# G1000_Base.net
KiCad netlist of a schematic drawn in EasyEDA
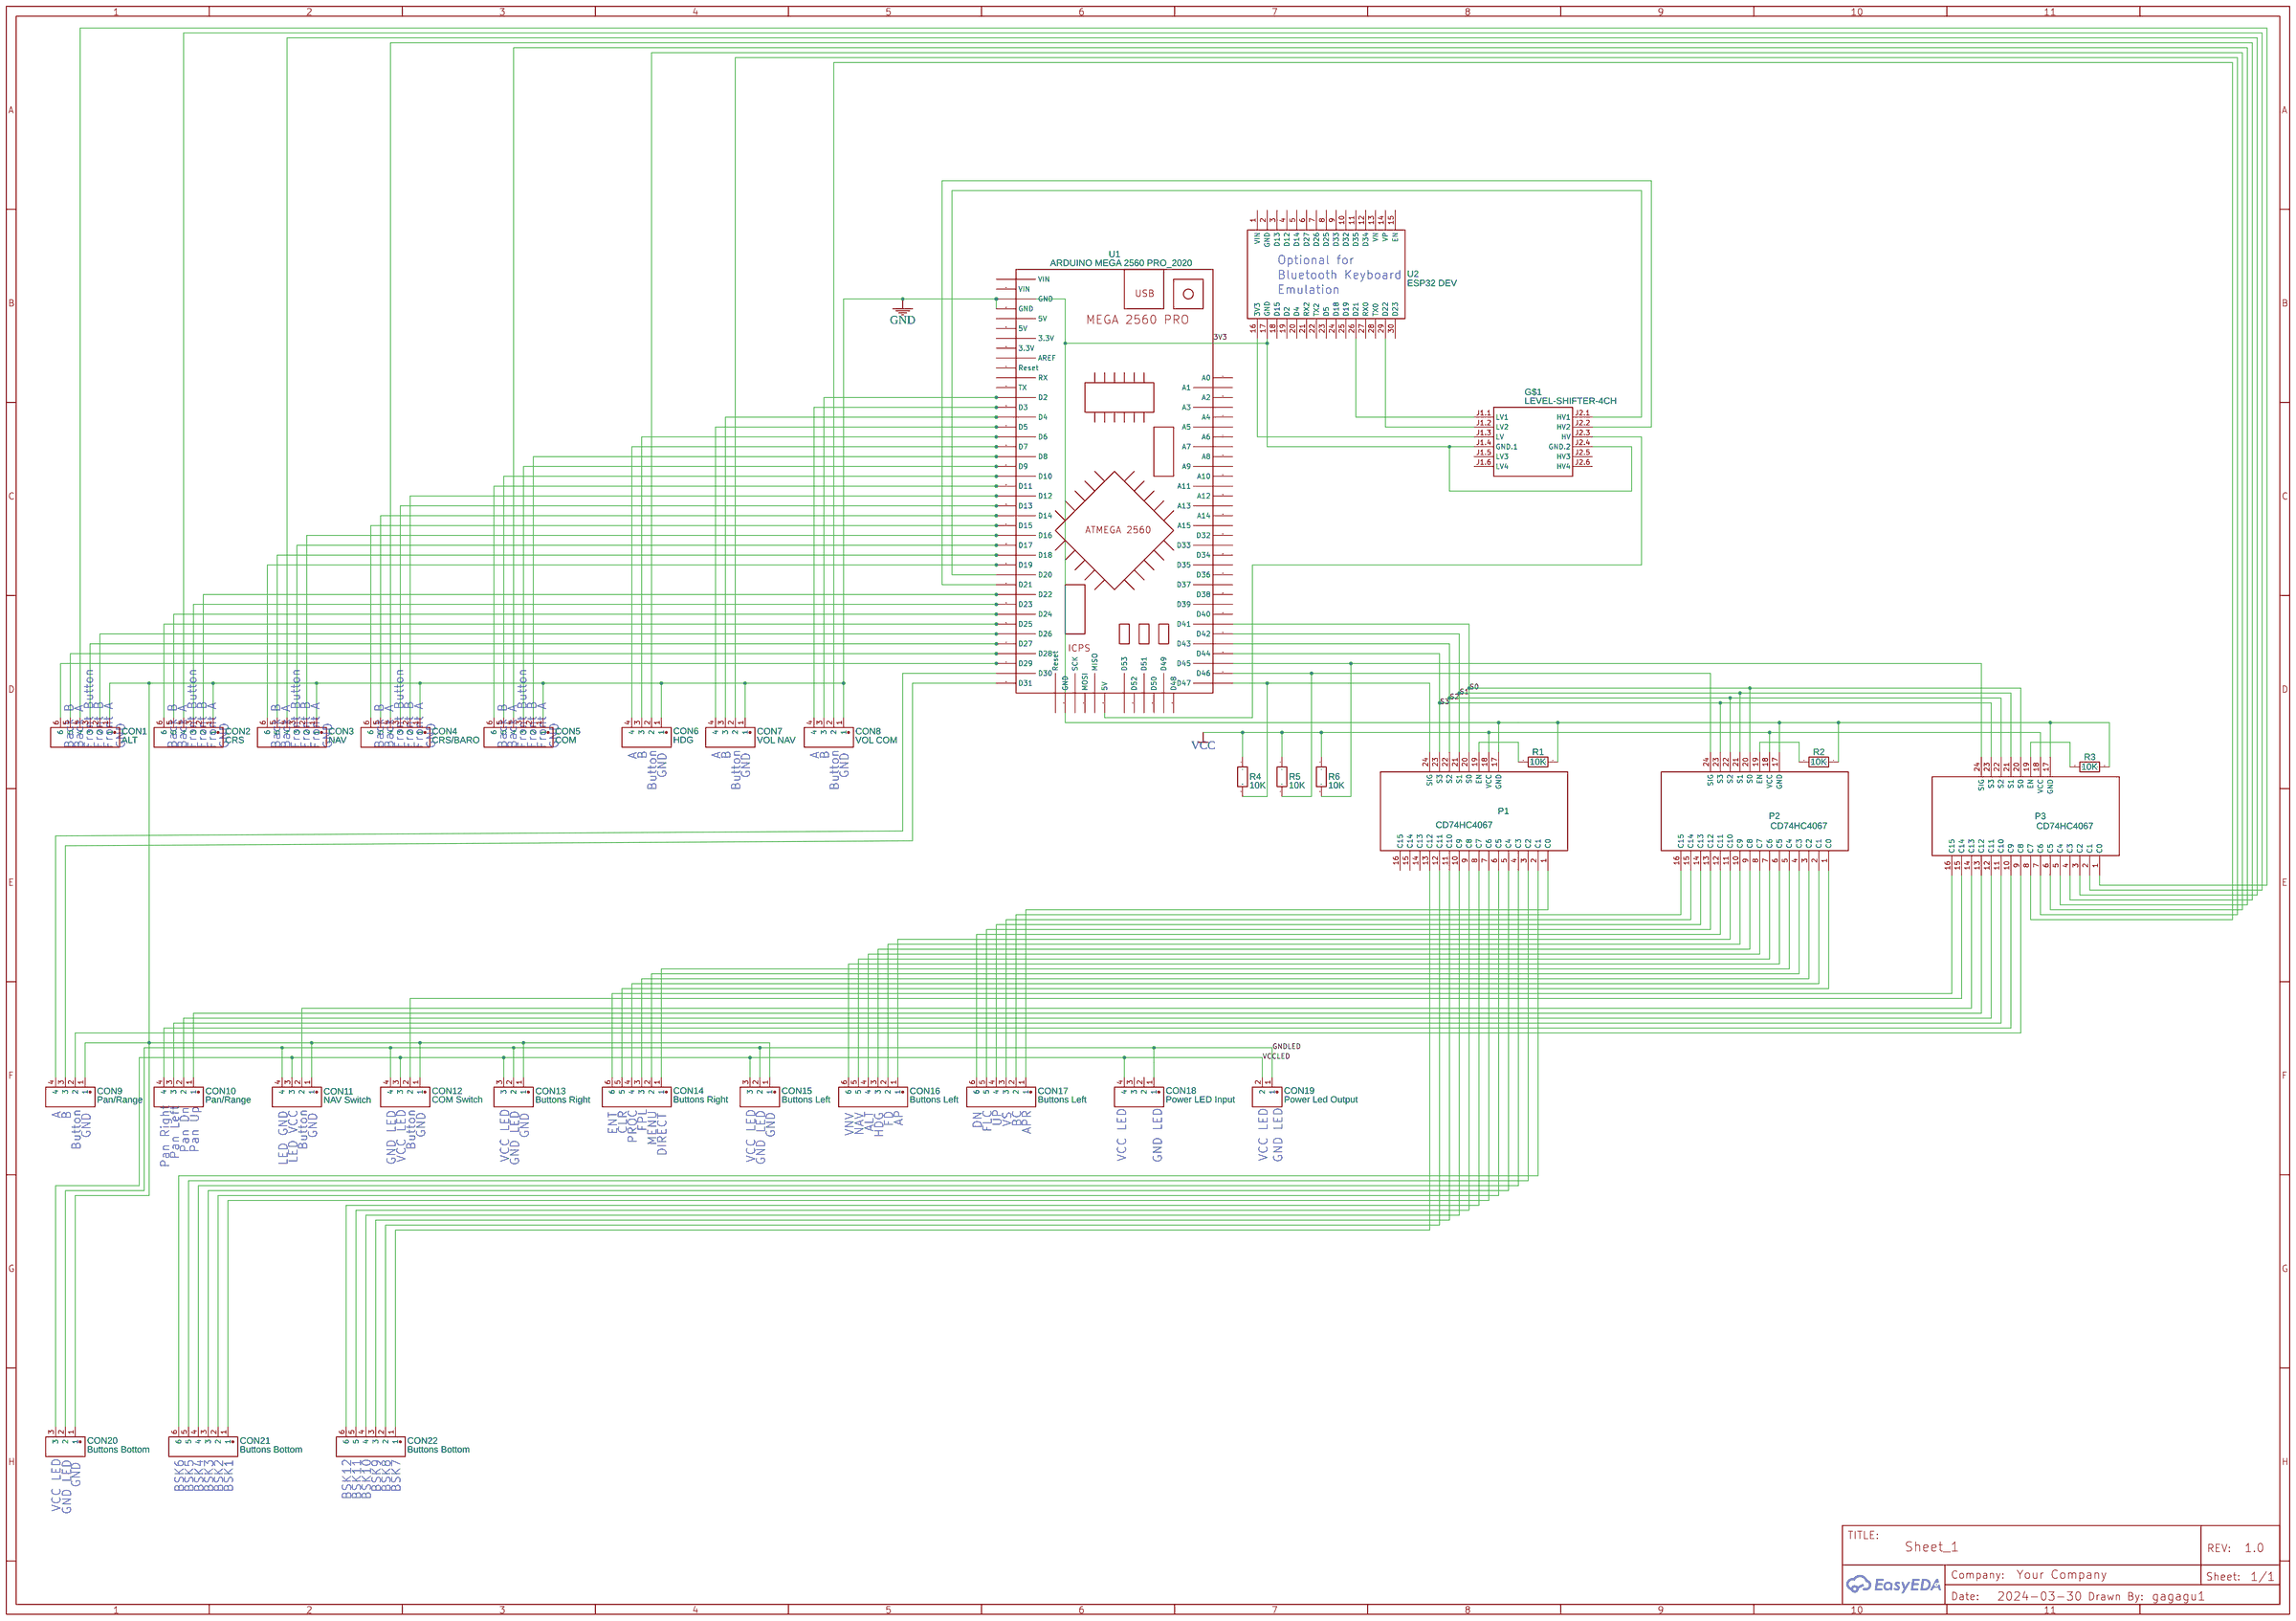
[diagram p0: schematic sheet]

(export (version "E")
  (design (tool "Eeschema 10.0.6"))
  (components
    (comp (ref "CON1")
      (value "ALT")
      (fields (field (name "Manufacturer Part") "XH-6A") (field (name "Manufacturer") "CAX"))
      (libsource (lib "") (part "ARUN-CONN-TH_XH-6A"))
    )
    (comp (ref "CON2")
      (value "CRS")
      (fields (field (name "Manufacturer Part") "XH-6A") (field (name "Manufacturer") "CAX"))
      (libsource (lib "") (part "ARUN-CONN-TH_XH-6A"))
    )
    (comp (ref "CON3")
      (value "NAV")
      (fields (field (name "Manufacturer Part") "XH-6A") (field (name "Manufacturer") "CAX"))
      (libsource (lib "") (part "ARUN-CONN-TH_XH-6A"))
    )
    (comp (ref "CON4")
      (value "CRS/BARO")
      (fields (field (name "Manufacturer Part") "XH-6A") (field (name "Manufacturer") "CAX"))
      (libsource (lib "") (part "ARUN-CONN-TH_XH-6A"))
    )
    (comp (ref "CON5")
      (value "COM")
      (fields (field (name "Manufacturer Part") "XH-6A") (field (name "Manufacturer") "CAX"))
      (libsource (lib "") (part "ARUN-CONN-TH_XH-6A"))
    )
    (comp (ref "CON6")
      (value "HDG")
      (fields (field (name "Manufacturer Part") "XH-4A绿色") (field (name "Manufacturer") "BOOMELE(博穆精密)"))
      (libsource (lib "") (part "ARUN-CONN-TH_XH-4A"))
    )
    (comp (ref "CON7")
      (value "VOL NAV")
      (fields (field (name "Manufacturer Part") "XH-4A绿色") (field (name "Manufacturer") "BOOMELE(博穆精密)"))
      (libsource (lib "") (part "ARUN-CONN-TH_XH-4A"))
    )
    (comp (ref "CON8")
      (value "VOL COM")
      (fields (field (name "Manufacturer Part") "XH-4A绿色") (field (name "Manufacturer") "BOOMELE(博穆精密)"))
      (libsource (lib "") (part "ARUN-CONN-TH_XH-4A"))
    )
    (comp (ref "CON9")
      (value "Pan/Range")
      (fields (field (name "Manufacturer Part") "XH-4A绿色") (field (name "Manufacturer") "BOOMELE(博穆精密)"))
      (libsource (lib "") (part "ARUN-CONN-TH_XH-4A"))
    )
    (comp (ref "CON10")
      (value "Pan/Range")
      (fields (field (name "Manufacturer Part") "XH-4A绿色") (field (name "Manufacturer") "BOOMELE(博穆精密)"))
      (libsource (lib "") (part "ARUN-CONN-TH_XH-4A"))
    )
    (comp (ref "CON11")
      (value "NAV Switch")
      (fields
        (field (name "Manufacturer Part") "A2541HWV-4P")
        (field (name "Manufacturer") "Changjiang Connectors")
      )
      (libsource (lib "") (part "1X4PIN"))
    )
    (comp (ref "CON12")
      (value "COM Switch")
      (fields
        (field (name "Manufacturer Part") "A2541HWV-4P")
        (field (name "Manufacturer") "Changjiang Connectors")
      )
      (libsource (lib "") (part "1X4PIN"))
    )
    (comp (ref "CON13")
      (value "Buttons Right")
      (fields (field (name "Manufacturer Part") "HC-XH-3A-G") (field (name "Manufacturer") "HCTL(华灿天禄)"))
      (libsource (lib "") (part "HC-XH-3A-G"))
    )
    (comp (ref "CON14")
      (value "Buttons Right")
      (fields (field (name "Manufacturer Part") "XH-6A") (field (name "Manufacturer") "CAX"))
      (libsource (lib "") (part "ARUN-CONN-TH_XH-6A"))
    )
    (comp (ref "CON15")
      (value "Buttons Left")
      (fields (field (name "Manufacturer Part") "HC-XH-3A-G") (field (name "Manufacturer") "HCTL(华灿天禄)"))
      (libsource (lib "") (part "HC-XH-3A-G"))
    )
    (comp (ref "CON16")
      (value "Buttons Left")
      (fields (field (name "Manufacturer Part") "XH-6A") (field (name "Manufacturer") "CAX"))
      (libsource (lib "") (part "ARUN-CONN-TH_XH-6A"))
    )
    (comp (ref "CON17")
      (value "Buttons Left")
      (fields (field (name "Manufacturer Part") "XH-6A") (field (name "Manufacturer") "CAX"))
      (libsource (lib "") (part "ARUN-CONN-TH_XH-6A"))
    )
    (comp (ref "CON18")
      (value "Power LED Input")
      (fields (field (name "Manufacturer Part") "XH-4A绿色") (field (name "Manufacturer") "BOOMELE(博穆精密)"))
      (libsource (lib "") (part "ARUN-CONN-TH_XH-4A"))
    )
    (comp (ref "CON19")
      (value "Power Led Output")
      (fields (field (name "Manufacturer Part") "HC-XH-2A-G") (field (name "Manufacturer") "HCTL(华灿天禄)"))
      (libsource (lib "") (part "HC-XH-2A-G"))
    )
    (comp (ref "CON20")
      (value "Buttons Bottom")
      (fields (field (name "Manufacturer Part") "HC-XH-3A-G") (field (name "Manufacturer") "HCTL(华灿天禄)"))
      (libsource (lib "") (part "HC-XH-3A-G"))
    )
    (comp (ref "CON21")
      (value "Buttons Bottom")
      (fields (field (name "Manufacturer Part") "XH-6A") (field (name "Manufacturer") "CAX"))
      (libsource (lib "") (part "ARUN-CONN-TH_XH-6A"))
    )
    (comp (ref "CON22")
      (value "Buttons Bottom")
      (fields (field (name "Manufacturer Part") "XH-6A") (field (name "Manufacturer") "CAX"))
      (libsource (lib "") (part "ARUN-CONN-TH_XH-6A"))
    )
    (comp (ref "G$1") (value "LEVEL-SHIFTER-4CH") (libsource (lib "") (part "LEVEL-SHIFTER-4CH")))
    (comp (ref "P1") (value "CD74HC4067") (libsource (lib "") (part "CD74HC4067")))
    (comp (ref "P2") (value "CD74HC4067") (libsource (lib "") (part "CD74HC4067")))
    (comp (ref "P3") (value "CD74HC4067") (libsource (lib "") (part "CD74HC4067")))
    (comp (ref "R1") (value "10K") (libsource (lib "") (part "R_AXIAL-0.4_EU")))
    (comp (ref "R2") (value "10K") (libsource (lib "") (part "R_AXIAL-0.4_EU")))
    (comp (ref "R3") (value "10K") (libsource (lib "") (part "R_AXIAL-0.4_EU")))
    (comp (ref "R4") (value "10K") (libsource (lib "") (part "R_AXIAL-0.4_EU_1")))
    (comp (ref "R5") (value "10K") (libsource (lib "") (part "R_AXIAL-0.4_EU_1")))
    (comp (ref "R6") (value "10K") (libsource (lib "") (part "R_AXIAL-0.4_EU_1")))
    (comp (ref "U1")
      (value "ARDUINO MEGA 2560 PRO_2020")
      (fields (field (name "Manufacturer Part") "Arduino Mega 2560 Pro Mini"))
      (libsource (lib "") (part "ARDUINO MEGA 2560 PRO_2020"))
    )
    (comp (ref "U2")
      (value "ESP32 DEV")
      (fields (field (name "Manufacturer Part") "ESP32"))
      (libsource (lib "") (part "ESP32 DEV"))
    )
  )
  (nets
    (net (code "2") (name "/GNDLED") (class "Default")
      (node (ref "CON11") (pin "4") (pinfunction "4_4") (pintype "unspecified"))
      (node (ref "CON12") (pin "4") (pinfunction "4_4") (pintype "unspecified"))
      (node (ref "CON13") (pin "2") (pinfunction "2_2") (pintype "unspecified"))
      (node (ref "CON15") (pin "2") (pinfunction "2_2") (pintype "unspecified"))
      (node (ref "CON18") (pin "1") (pinfunction "1_1") (pintype "unspecified"))
      (node (ref "CON19") (pin "1") (pinfunction "1_1") (pintype "unspecified"))
      (node (ref "CON20") (pin "2") (pinfunction "2_2") (pintype "unspecified"))
    )
    (net (code "3") (name "/S0") (class "Default")
      (node (ref "P1") (pin "20") (pinfunction "S0_20") (pintype "unspecified"))
      (node (ref "P2") (pin "20") (pinfunction "S0_20") (pintype "unspecified"))
      (node (ref "P3") (pin "20") (pinfunction "S0_20") (pintype "unspecified"))
      (node (ref "U1") (pin "26") (pinfunction "D41_26") (pintype "unspecified"))
    )
    (net (code "4") (name "/S1") (class "Default")
      (node (ref "P1") (pin "21") (pinfunction "S1_21") (pintype "unspecified"))
      (node (ref "P2") (pin "21") (pinfunction "S1_21") (pintype "unspecified"))
      (node (ref "P3") (pin "21") (pinfunction "S1_21") (pintype "unspecified"))
      (node (ref "U1") (pin "27") (pinfunction "D42_27") (pintype "unspecified"))
    )
    (net (code "5") (name "/S2") (class "Default")
      (node (ref "P1") (pin "22") (pinfunction "S2_22") (pintype "unspecified"))
      (node (ref "P2") (pin "22") (pinfunction "S2_22") (pintype "unspecified"))
      (node (ref "P3") (pin "22") (pinfunction "S2_22") (pintype "unspecified"))
      (node (ref "U1") (pin "28") (pinfunction "D43_28") (pintype "unspecified"))
    )
    (net (code "6") (name "/S3") (class "Default")
      (node (ref "P1") (pin "23") (pinfunction "S3_23") (pintype "unspecified"))
      (node (ref "P2") (pin "23") (pinfunction "S3_23") (pintype "unspecified"))
      (node (ref "P3") (pin "23") (pinfunction "S3_23") (pintype "unspecified"))
      (node (ref "U1") (pin "29") (pinfunction "D44_29") (pintype "unspecified"))
    )
    (net (code "7") (name "/VCCLED") (class "Default")
      (node (ref "CON11") (pin "3") (pinfunction "3_3") (pintype "unspecified"))
      (node (ref "CON12") (pin "3") (pinfunction "3_3") (pintype "unspecified"))
      (node (ref "CON13") (pin "3") (pinfunction "3_3") (pintype "unspecified"))
      (node (ref "CON15") (pin "3") (pinfunction "3_3") (pintype "unspecified"))
      (node (ref "CON18") (pin "4") (pinfunction "4_4") (pintype "unspecified"))
      (node (ref "CON19") (pin "2") (pinfunction "2_2") (pintype "unspecified"))
      (node (ref "CON20") (pin "3") (pinfunction "3_3") (pintype "unspecified"))
    )
    (net (code "8") (name "GND") (class "Default")
      (node (ref "CON1") (pin "1") (pinfunction "1_1") (pintype "unspecified"))
      (node (ref "CON11") (pin "1") (pinfunction "1_1") (pintype "unspecified"))
      (node (ref "CON12") (pin "1") (pinfunction "1_1") (pintype "unspecified"))
      (node (ref "CON13") (pin "1") (pinfunction "1_1") (pintype "unspecified"))
      (node (ref "CON15") (pin "1") (pinfunction "1_1") (pintype "unspecified"))
      (node (ref "CON2") (pin "1") (pinfunction "1_1") (pintype "unspecified"))
      (node (ref "CON20") (pin "1") (pinfunction "1_1") (pintype "unspecified"))
      (node (ref "CON3") (pin "1") (pinfunction "1_1") (pintype "unspecified"))
      (node (ref "CON4") (pin "1") (pinfunction "1_1") (pintype "unspecified"))
      (node (ref "CON5") (pin "1") (pinfunction "1_1") (pintype "unspecified"))
      (node (ref "CON6") (pin "1") (pinfunction "1_1") (pintype "unspecified"))
      (node (ref "CON7") (pin "1") (pinfunction "1_1") (pintype "unspecified"))
      (node (ref "CON8") (pin "1") (pinfunction "1_1") (pintype "unspecified"))
      (node (ref "CON9") (pin "1") (pinfunction "1_1") (pintype "unspecified"))
      (node (ref "G$1") (pin "J1.4") (pinfunction "GND.1_J1.4") (pintype "bidirectional"))
      (node (ref "G$1") (pin "J2.4") (pinfunction "GND.2_J2.4") (pintype "bidirectional"))
      (node (ref "P1") (pin "17") (pinfunction "GND_17") (pintype "unspecified"))
      (node (ref "P2") (pin "17") (pinfunction "GND_17") (pintype "unspecified"))
      (node (ref "P3") (pin "17") (pinfunction "GND_17") (pintype "unspecified"))
      (node (ref "R1") (pin "1") (pinfunction "1_1") (pintype "unspecified"))
      (node (ref "R2") (pin "1") (pinfunction "1_1") (pintype "unspecified"))
      (node (ref "R3") (pin "1") (pinfunction "1_1") (pintype "unspecified"))
      (node (ref "U1") (pin "43") (pinfunction "GND_43") (pintype "unspecified"))
      (node (ref "U1") (pin "83") (pinfunction "GND_83") (pintype "unspecified"))
      (node (ref "U1") (pin "84") (pinfunction "GND_84") (pintype "unspecified"))
      (node (ref "U2") (pin "17") (pinfunction "GND_17") (pintype "passive"))
    )
    (net (code "9") (name "Net-(G$1-HV)") (class "Default")
      (node (ref "G$1") (pin "J2.3") (pinfunction "HV_J2.3") (pintype "bidirectional"))
      (node (ref "U1") (pin "39") (pinfunction "5V_39") (pintype "unspecified"))
    )
    (net (code "10") (name "Net-(G$1-HV1)") (class "Default")
      (node (ref "G$1") (pin "J2.1") (pinfunction "HV1_J2.1") (pintype "bidirectional"))
      (node (ref "U1") (pin "56") (pinfunction "D20_56") (pintype "unspecified"))
    )
    (net (code "11") (name "Net-(G$1-HV2)") (class "Default")
      (node (ref "G$1") (pin "J2.2") (pinfunction "HV2_J2.2") (pintype "bidirectional"))
      (node (ref "U1") (pin "55") (pinfunction "D21_55") (pintype "unspecified"))
    )
    (net (code "12") (name "Net-(G$1-LV)") (class "Default")
      (node (ref "G$1") (pin "J1.3") (pinfunction "LV_J1.3") (pintype "bidirectional"))
      (node (ref "U2") (pin "16") (pinfunction "3V3_16") (pintype "passive"))
    )
    (net (code "13") (name "Net-(G$1-LV1)") (class "Default")
      (node (ref "G$1") (pin "J1.1") (pinfunction "LV1_J1.1") (pintype "bidirectional"))
      (node (ref "U2") (pin "26") (pinfunction "D21_26") (pintype "bidirectional"))
    )
    (net (code "14") (name "Net-(G$1-LV2)") (class "Default")
      (node (ref "G$1") (pin "J1.2") (pinfunction "LV2_J1.2") (pintype "bidirectional"))
      (node (ref "U2") (pin "29") (pinfunction "D22_29") (pintype "bidirectional"))
    )
    (net (code "15") (name "Net-(P1-C0)") (class "Default")
      (node (ref "CON17") (pin "1") (pinfunction "1_1") (pintype "unspecified"))
      (node (ref "P1") (pin "1") (pinfunction "C0_1") (pintype "unspecified"))
    )
    (net (code "16") (name "Net-(P1-C1)") (class "Default")
      (node (ref "CON21") (pin "6") (pinfunction "6_6") (pintype "unspecified"))
      (node (ref "P1") (pin "2") (pinfunction "C1_2") (pintype "unspecified"))
    )
    (net (code "17") (name "Net-(P1-C2)") (class "Default")
      (node (ref "CON21") (pin "5") (pinfunction "5_5") (pintype "unspecified"))
      (node (ref "P1") (pin "3") (pinfunction "C2_3") (pintype "unspecified"))
    )
    (net (code "18") (name "Net-(P1-C3)") (class "Default")
      (node (ref "CON21") (pin "4") (pinfunction "4_4") (pintype "unspecified"))
      (node (ref "P1") (pin "4") (pinfunction "C3_4") (pintype "unspecified"))
    )
    (net (code "19") (name "Net-(P1-C4)") (class "Default")
      (node (ref "CON21") (pin "3") (pinfunction "3_3") (pintype "unspecified"))
      (node (ref "P1") (pin "5") (pinfunction "C4_5") (pintype "unspecified"))
    )
    (net (code "20") (name "Net-(P1-C5)") (class "Default")
      (node (ref "CON21") (pin "2") (pinfunction "2_2") (pintype "unspecified"))
      (node (ref "P1") (pin "6") (pinfunction "C5_6") (pintype "unspecified"))
    )
    (net (code "21") (name "Net-(P1-C6)") (class "Default")
      (node (ref "CON21") (pin "1") (pinfunction "1_1") (pintype "unspecified"))
      (node (ref "P1") (pin "7") (pinfunction "C6_7") (pintype "unspecified"))
    )
    (net (code "22") (name "Net-(P1-C7)") (class "Default")
      (node (ref "CON22") (pin "6") (pinfunction "6_6") (pintype "unspecified"))
      (node (ref "P1") (pin "8") (pinfunction "C7_8") (pintype "unspecified"))
    )
    (net (code "23") (name "Net-(P1-C8)") (class "Default")
      (node (ref "CON22") (pin "5") (pinfunction "5_5") (pintype "unspecified"))
      (node (ref "P1") (pin "9") (pinfunction "C8_9") (pintype "unspecified"))
    )
    (net (code "24") (name "Net-(P1-C9)") (class "Default")
      (node (ref "CON22") (pin "4") (pinfunction "4_4") (pintype "unspecified"))
      (node (ref "P1") (pin "10") (pinfunction "C9_10") (pintype "unspecified"))
    )
    (net (code "25") (name "Net-(P1-C10)") (class "Default")
      (node (ref "CON22") (pin "3") (pinfunction "3_3") (pintype "unspecified"))
      (node (ref "P1") (pin "11") (pinfunction "C10_11") (pintype "unspecified"))
    )
    (net (code "26") (name "Net-(P1-C11)") (class "Default")
      (node (ref "CON22") (pin "2") (pinfunction "2_2") (pintype "unspecified"))
      (node (ref "P1") (pin "12") (pinfunction "C11_12") (pintype "unspecified"))
    )
    (net (code "27") (name "Net-(P1-C12)") (class "Default")
      (node (ref "CON22") (pin "1") (pinfunction "1_1") (pintype "unspecified"))
      (node (ref "P1") (pin "13") (pinfunction "C12_13") (pintype "unspecified"))
    )
    (net (code "28") (name "Net-(P1-EN)") (class "Default")
      (node (ref "P1") (pin "19") (pinfunction "EN_19") (pintype "unspecified"))
      (node (ref "R1") (pin "2") (pinfunction "2_2") (pintype "unspecified"))
    )
    (net (code "29") (name "Net-(P1-SIG)") (class "Default")
      (node (ref "P1") (pin "24") (pinfunction "SIG_24") (pintype "unspecified"))
      (node (ref "R4") (pin "2") (pinfunction "2_2") (pintype "unspecified"))
      (node (ref "U1") (pin "32") (pinfunction "D47_32") (pintype "unspecified"))
    )
    (net (code "30") (name "Net-(P2-C0)") (class "Default")
      (node (ref "CON14") (pin "5") (pinfunction "5_5") (pintype "unspecified"))
      (node (ref "P2") (pin "1") (pinfunction "C0_1") (pintype "unspecified"))
    )
    (net (code "31") (name "Net-(P2-C1)") (class "Default")
      (node (ref "CON14") (pin "4") (pinfunction "4_4") (pintype "unspecified"))
      (node (ref "P2") (pin "2") (pinfunction "C1_2") (pintype "unspecified"))
    )
    (net (code "32") (name "Net-(P2-C2)") (class "Default")
      (node (ref "CON14") (pin "3") (pinfunction "3_3") (pintype "unspecified"))
      (node (ref "P2") (pin "3") (pinfunction "C2_3") (pintype "unspecified"))
    )
    (net (code "33") (name "Net-(P2-C3)") (class "Default")
      (node (ref "CON14") (pin "2") (pinfunction "2_2") (pintype "unspecified"))
      (node (ref "P2") (pin "4") (pinfunction "C3_4") (pintype "unspecified"))
    )
    (net (code "34") (name "Net-(P2-C4)") (class "Default")
      (node (ref "CON14") (pin "1") (pinfunction "1_1") (pintype "unspecified"))
      (node (ref "P2") (pin "5") (pinfunction "C4_5") (pintype "unspecified"))
    )
    (net (code "35") (name "Net-(P2-C5)") (class "Default")
      (node (ref "CON16") (pin "6") (pinfunction "6_6") (pintype "unspecified"))
      (node (ref "P2") (pin "6") (pinfunction "C5_6") (pintype "unspecified"))
    )
    (net (code "36") (name "Net-(P2-C6)") (class "Default")
      (node (ref "CON16") (pin "5") (pinfunction "5_5") (pintype "unspecified"))
      (node (ref "P2") (pin "7") (pinfunction "C6_7") (pintype "unspecified"))
    )
    (net (code "37") (name "Net-(P2-C7)") (class "Default")
      (node (ref "CON16") (pin "4") (pinfunction "4_4") (pintype "unspecified"))
      (node (ref "P2") (pin "8") (pinfunction "C7_8") (pintype "unspecified"))
    )
    (net (code "38") (name "Net-(P2-C8)") (class "Default")
      (node (ref "CON16") (pin "3") (pinfunction "3_3") (pintype "unspecified"))
      (node (ref "P2") (pin "9") (pinfunction "C8_9") (pintype "unspecified"))
    )
    (net (code "39") (name "Net-(P2-C9)") (class "Default")
      (node (ref "CON16") (pin "2") (pinfunction "2_2") (pintype "unspecified"))
      (node (ref "P2") (pin "10") (pinfunction "C9_10") (pintype "unspecified"))
    )
    (net (code "40") (name "Net-(P2-C10)") (class "Default")
      (node (ref "CON16") (pin "1") (pinfunction "1_1") (pintype "unspecified"))
      (node (ref "P2") (pin "11") (pinfunction "C10_11") (pintype "unspecified"))
    )
    (net (code "41") (name "Net-(P2-C11)") (class "Default")
      (node (ref "CON17") (pin "6") (pinfunction "6_6") (pintype "unspecified"))
      (node (ref "P2") (pin "12") (pinfunction "C11_12") (pintype "unspecified"))
    )
    (net (code "42") (name "Net-(P2-C12)") (class "Default")
      (node (ref "CON17") (pin "5") (pinfunction "5_5") (pintype "unspecified"))
      (node (ref "P2") (pin "13") (pinfunction "C12_13") (pintype "unspecified"))
    )
    (net (code "43") (name "Net-(P2-C13)") (class "Default")
      (node (ref "CON17") (pin "4") (pinfunction "4_4") (pintype "unspecified"))
      (node (ref "P2") (pin "14") (pinfunction "C13_14") (pintype "unspecified"))
    )
    (net (code "44") (name "Net-(P2-C14)") (class "Default")
      (node (ref "CON17") (pin "3") (pinfunction "3_3") (pintype "unspecified"))
      (node (ref "P2") (pin "15") (pinfunction "C14_15") (pintype "unspecified"))
    )
    (net (code "45") (name "Net-(P2-C15)") (class "Default")
      (node (ref "CON17") (pin "2") (pinfunction "2_2") (pintype "unspecified"))
      (node (ref "P2") (pin "16") (pinfunction "C15_16") (pintype "unspecified"))
    )
    (net (code "46") (name "Net-(P2-EN)") (class "Default")
      (node (ref "P2") (pin "19") (pinfunction "EN_19") (pintype "unspecified"))
      (node (ref "R2") (pin "2") (pinfunction "2_2") (pintype "unspecified"))
    )
    (net (code "47") (name "Net-(P2-SIG)") (class "Default")
      (node (ref "P2") (pin "24") (pinfunction "SIG_24") (pintype "unspecified"))
      (node (ref "R5") (pin "2") (pinfunction "2_2") (pintype "unspecified"))
      (node (ref "U1") (pin "31") (pinfunction "D46_31") (pintype "unspecified"))
    )
    (net (code "48") (name "Net-(P3-C0)") (class "Default")
      (node (ref "CON1") (pin "4") (pinfunction "4_4") (pintype "unspecified"))
      (node (ref "P3") (pin "1") (pinfunction "C0_1") (pintype "unspecified"))
    )
    (net (code "49") (name "Net-(P3-C1)") (class "Default")
      (node (ref "CON2") (pin "4") (pinfunction "4_4") (pintype "unspecified"))
      (node (ref "P3") (pin "2") (pinfunction "C1_2") (pintype "unspecified"))
    )
    (net (code "50") (name "Net-(P3-C2)") (class "Default")
      (node (ref "CON3") (pin "4") (pinfunction "4_4") (pintype "unspecified"))
      (node (ref "P3") (pin "3") (pinfunction "C2_3") (pintype "unspecified"))
    )
    (net (code "51") (name "Net-(P3-C3)") (class "Default")
      (node (ref "CON4") (pin "4") (pinfunction "4_4") (pintype "unspecified"))
      (node (ref "P3") (pin "4") (pinfunction "C3_4") (pintype "unspecified"))
    )
    (net (code "52") (name "Net-(P3-C4)") (class "Default")
      (node (ref "CON5") (pin "4") (pinfunction "4_4") (pintype "unspecified"))
      (node (ref "P3") (pin "5") (pinfunction "C4_5") (pintype "unspecified"))
    )
    (net (code "53") (name "Net-(P3-C5)") (class "Default")
      (node (ref "CON6") (pin "2") (pinfunction "2_2") (pintype "unspecified"))
      (node (ref "P3") (pin "6") (pinfunction "C5_6") (pintype "unspecified"))
    )
    (net (code "54") (name "Net-(P3-C6)") (class "Default")
      (node (ref "CON7") (pin "2") (pinfunction "2_2") (pintype "unspecified"))
      (node (ref "P3") (pin "7") (pinfunction "C6_7") (pintype "unspecified"))
    )
    (net (code "55") (name "Net-(P3-C7)") (class "Default")
      (node (ref "CON8") (pin "2") (pinfunction "2_2") (pintype "unspecified"))
      (node (ref "P3") (pin "8") (pinfunction "C7_8") (pintype "unspecified"))
    )
    (net (code "56") (name "Net-(P3-C8)") (class "Default")
      (node (ref "CON9") (pin "2") (pinfunction "2_2") (pintype "unspecified"))
      (node (ref "P3") (pin "9") (pinfunction "C8_9") (pintype "unspecified"))
    )
    (net (code "57") (name "Net-(P3-C9)") (class "Default")
      (node (ref "CON10") (pin "4") (pinfunction "4_4") (pintype "unspecified"))
      (node (ref "P3") (pin "10") (pinfunction "C9_10") (pintype "unspecified"))
    )
    (net (code "58") (name "Net-(P3-C10)") (class "Default")
      (node (ref "CON10") (pin "3") (pinfunction "3_3") (pintype "unspecified"))
      (node (ref "P3") (pin "11") (pinfunction "C10_11") (pintype "unspecified"))
    )
    (net (code "59") (name "Net-(P3-C11)") (class "Default")
      (node (ref "CON10") (pin "2") (pinfunction "2_2") (pintype "unspecified"))
      (node (ref "P3") (pin "12") (pinfunction "C11_12") (pintype "unspecified"))
    )
    (net (code "60") (name "Net-(P3-C12)") (class "Default")
      (node (ref "CON10") (pin "1") (pinfunction "1_1") (pintype "unspecified"))
      (node (ref "P3") (pin "13") (pinfunction "C12_13") (pintype "unspecified"))
    )
    (net (code "61") (name "Net-(P3-C13)") (class "Default")
      (node (ref "CON11") (pin "2") (pinfunction "2_2") (pintype "unspecified"))
      (node (ref "P3") (pin "14") (pinfunction "C13_14") (pintype "unspecified"))
    )
    (net (code "62") (name "Net-(P3-C14)") (class "Default")
      (node (ref "CON12") (pin "2") (pinfunction "2_2") (pintype "unspecified"))
      (node (ref "P3") (pin "15") (pinfunction "C14_15") (pintype "unspecified"))
    )
    (net (code "63") (name "Net-(P3-C15)") (class "Default")
      (node (ref "CON14") (pin "6") (pinfunction "6_6") (pintype "unspecified"))
      (node (ref "P3") (pin "16") (pinfunction "C15_16") (pintype "unspecified"))
    )
    (net (code "64") (name "Net-(P3-EN)") (class "Default")
      (node (ref "P3") (pin "19") (pinfunction "EN_19") (pintype "unspecified"))
      (node (ref "R3") (pin "2") (pinfunction "2_2") (pintype "unspecified"))
    )
    (net (code "65") (name "Net-(P3-SIG)") (class "Default")
      (node (ref "P3") (pin "24") (pinfunction "SIG_24") (pintype "unspecified"))
      (node (ref "R6") (pin "2") (pinfunction "2_2") (pintype "unspecified"))
      (node (ref "U1") (pin "30") (pinfunction "D45_30") (pintype "unspecified"))
    )
    (net (code "66") (name "Net-(U1-D2)") (class "Default")
      (node (ref "CON8") (pin "3") (pinfunction "3_3") (pintype "unspecified"))
      (node (ref "U1") (pin "74") (pinfunction "D2_74") (pintype "unspecified"))
    )
    (net (code "67") (name "Net-(U1-D3)") (class "Default")
      (node (ref "CON8") (pin "4") (pinfunction "4_4") (pintype "unspecified"))
      (node (ref "U1") (pin "73") (pinfunction "D3_73") (pintype "unspecified"))
    )
    (net (code "68") (name "Net-(U1-D4)") (class "Default")
      (node (ref "CON7") (pin "3") (pinfunction "3_3") (pintype "unspecified"))
      (node (ref "U1") (pin "72") (pinfunction "D4_72") (pintype "unspecified"))
    )
    (net (code "69") (name "Net-(U1-D5)") (class "Default")
      (node (ref "CON7") (pin "4") (pinfunction "4_4") (pintype "unspecified"))
      (node (ref "U1") (pin "71") (pinfunction "D5_71") (pintype "unspecified"))
    )
    (net (code "70") (name "Net-(U1-D6)") (class "Default")
      (node (ref "CON6") (pin "3") (pinfunction "3_3") (pintype "unspecified"))
      (node (ref "U1") (pin "70") (pinfunction "D6_70") (pintype "unspecified"))
    )
    (net (code "71") (name "Net-(U1-D7)") (class "Default")
      (node (ref "CON6") (pin "4") (pinfunction "4_4") (pintype "unspecified"))
      (node (ref "U1") (pin "69") (pinfunction "D7_69") (pintype "unspecified"))
    )
    (net (code "72") (name "Net-(U1-D8)") (class "Default")
      (node (ref "CON5") (pin "2") (pinfunction "2_2") (pintype "unspecified"))
      (node (ref "U1") (pin "68") (pinfunction "D8_68") (pintype "unspecified"))
    )
    (net (code "73") (name "Net-(U1-D9)") (class "Default")
      (node (ref "CON5") (pin "3") (pinfunction "3_3") (pintype "unspecified"))
      (node (ref "U1") (pin "67") (pinfunction "D9_67") (pintype "unspecified"))
    )
    (net (code "74") (name "Net-(U1-D10)") (class "Default")
      (node (ref "CON5") (pin "5") (pinfunction "5_5") (pintype "unspecified"))
      (node (ref "U1") (pin "66") (pinfunction "D10_66") (pintype "unspecified"))
    )
    (net (code "75") (name "Net-(U1-D11)") (class "Default")
      (node (ref "CON5") (pin "6") (pinfunction "6_6") (pintype "unspecified"))
      (node (ref "U1") (pin "65") (pinfunction "D11_65") (pintype "unspecified"))
    )
    (net (code "76") (name "Net-(U1-D12)") (class "Default")
      (node (ref "CON4") (pin "2") (pinfunction "2_2") (pintype "unspecified"))
      (node (ref "U1") (pin "64") (pinfunction "D12_64") (pintype "unspecified"))
    )
    (net (code "77") (name "Net-(U1-D13)") (class "Default")
      (node (ref "CON4") (pin "3") (pinfunction "3_3") (pintype "unspecified"))
      (node (ref "U1") (pin "63") (pinfunction "D13_63") (pintype "unspecified"))
    )
    (net (code "78") (name "Net-(U1-D14)") (class "Default")
      (node (ref "CON4") (pin "5") (pinfunction "5_5") (pintype "unspecified"))
      (node (ref "U1") (pin "62") (pinfunction "D14_62") (pintype "unspecified"))
    )
    (net (code "79") (name "Net-(U1-D15)") (class "Default")
      (node (ref "CON4") (pin "6") (pinfunction "6_6") (pintype "unspecified"))
      (node (ref "U1") (pin "61") (pinfunction "D15_61") (pintype "unspecified"))
    )
    (net (code "80") (name "Net-(U1-D16)") (class "Default")
      (node (ref "CON3") (pin "2") (pinfunction "2_2") (pintype "unspecified"))
      (node (ref "U1") (pin "60") (pinfunction "D16_60") (pintype "unspecified"))
    )
    (net (code "81") (name "Net-(U1-D17)") (class "Default")
      (node (ref "CON3") (pin "3") (pinfunction "3_3") (pintype "unspecified"))
      (node (ref "U1") (pin "59") (pinfunction "D17_59") (pintype "unspecified"))
    )
    (net (code "82") (name "Net-(U1-D18)") (class "Default")
      (node (ref "CON3") (pin "5") (pinfunction "5_5") (pintype "unspecified"))
      (node (ref "U1") (pin "58") (pinfunction "D18_58") (pintype "unspecified"))
    )
    (net (code "83") (name "Net-(U1-D19)") (class "Default")
      (node (ref "CON3") (pin "6") (pinfunction "6_6") (pintype "unspecified"))
      (node (ref "U1") (pin "57") (pinfunction "D19_57") (pintype "unspecified"))
    )
    (net (code "84") (name "Net-(U1-D22)") (class "Default")
      (node (ref "CON2") (pin "2") (pinfunction "2_2") (pintype "unspecified"))
      (node (ref "U1") (pin "54") (pinfunction "D22_54") (pintype "unspecified"))
    )
    (net (code "85") (name "Net-(U1-D23)") (class "Default")
      (node (ref "CON2") (pin "3") (pinfunction "3_3") (pintype "unspecified"))
      (node (ref "U1") (pin "53") (pinfunction "D23_53") (pintype "unspecified"))
    )
    (net (code "86") (name "Net-(U1-D24)") (class "Default")
      (node (ref "CON2") (pin "5") (pinfunction "5_5") (pintype "unspecified"))
      (node (ref "U1") (pin "52") (pinfunction "D24_52") (pintype "unspecified"))
    )
    (net (code "87") (name "Net-(U1-D25)") (class "Default")
      (node (ref "CON2") (pin "6") (pinfunction "6_6") (pintype "unspecified"))
      (node (ref "U1") (pin "51") (pinfunction "D25_51") (pintype "unspecified"))
    )
    (net (code "88") (name "Net-(U1-D26)") (class "Default")
      (node (ref "CON1") (pin "2") (pinfunction "2_2") (pintype "unspecified"))
      (node (ref "U1") (pin "50") (pinfunction "D26_50") (pintype "unspecified"))
    )
    (net (code "89") (name "Net-(U1-D27)") (class "Default")
      (node (ref "CON1") (pin "3") (pinfunction "3_3") (pintype "unspecified"))
      (node (ref "U1") (pin "49") (pinfunction "D27_49") (pintype "unspecified"))
    )
    (net (code "90") (name "Net-(U1-D28)") (class "Default")
      (node (ref "CON1") (pin "5") (pinfunction "5_5") (pintype "unspecified"))
      (node (ref "U1") (pin "48") (pinfunction "D28_48") (pintype "unspecified"))
    )
    (net (code "91") (name "Net-(U1-D29)") (class "Default")
      (node (ref "CON1") (pin "6") (pinfunction "6_6") (pintype "unspecified"))
      (node (ref "U1") (pin "47") (pinfunction "D29_47") (pintype "unspecified"))
    )
    (net (code "92") (name "Net-(U1-D30)") (class "Default")
      (node (ref "CON9") (pin "4") (pinfunction "4_4") (pintype "unspecified"))
      (node (ref "U1") (pin "46") (pinfunction "D30_46") (pintype "unspecified"))
    )
    (net (code "93") (name "Net-(U1-D31)") (class "Default")
      (node (ref "CON9") (pin "3") (pinfunction "3_3") (pintype "unspecified"))
      (node (ref "U1") (pin "45") (pinfunction "D31_45") (pintype "unspecified"))
    )
    (net (code "94") (name "VCC") (class "Default")
      (node (ref "P1") (pin "18") (pinfunction "VCC_18") (pintype "unspecified"))
      (node (ref "P2") (pin "18") (pinfunction "VCC_18") (pintype "unspecified"))
      (node (ref "P3") (pin "18") (pinfunction "VCC_18") (pintype "unspecified"))
      (node (ref "R4") (pin "1") (pinfunction "1_1") (pintype "unspecified"))
      (node (ref "R5") (pin "1") (pinfunction "1_1") (pintype "unspecified"))
      (node (ref "R6") (pin "1") (pinfunction "1_1") (pintype "unspecified"))
    )
    (net (code "95") (name "unconnected-(CON18-Pad2)") (class "Default")
      (node (ref "CON18") (pin "2") (pinfunction "2_2") (pintype "unspecified"))
    )
    (net (code "96") (name "unconnected-(CON18-Pad3)") (class "Default")
      (node (ref "CON18") (pin "3") (pinfunction "3_3") (pintype "unspecified"))
    )
    (net (code "97") (name "unconnected-(G$1-HV3-PadJ2.5)") (class "Default")
      (node (ref "G$1") (pin "J2.5") (pinfunction "HV3_J2.5") (pintype "bidirectional"))
    )
    (net (code "98") (name "unconnected-(G$1-HV4-PadJ2.6)") (class "Default")
      (node (ref "G$1") (pin "J2.6") (pinfunction "HV4_J2.6") (pintype "bidirectional"))
    )
    (net (code "99") (name "unconnected-(G$1-LV3-PadJ1.5)") (class "Default")
      (node (ref "G$1") (pin "J1.5") (pinfunction "LV3_J1.5") (pintype "bidirectional"))
    )
    (net (code "100") (name "unconnected-(G$1-LV4-PadJ1.6)") (class "Default")
      (node (ref "G$1") (pin "J1.6") (pinfunction "LV4_J1.6") (pintype "bidirectional"))
    )
    (net (code "101") (name "unconnected-(P1-C13-Pad14)") (class "Default")
      (node (ref "P1") (pin "14") (pinfunction "C13_14") (pintype "unspecified"))
    )
    (net (code "102") (name "unconnected-(P1-C14-Pad15)") (class "Default")
      (node (ref "P1") (pin "15") (pinfunction "C14_15") (pintype "unspecified"))
    )
    (net (code "103") (name "unconnected-(P1-C15-Pad16)") (class "Default")
      (node (ref "P1") (pin "16") (pinfunction "C15_16") (pintype "unspecified"))
    )
    (net (code "104") (name "unconnected-(U1-3.3V-Pad79)") (class "Default")
      (node (ref "U1") (pin "79") (pinfunction "3.3V_79") (pintype "unspecified"))
    )
    (net (code "105") (name "unconnected-(U1-3.3V-Pad80)") (class "Default")
      (node (ref "U1") (pin "80") (pinfunction "3.3V_80") (pintype "unspecified"))
    )
    (net (code "106") (name "unconnected-(U1-5V-Pad81)") (class "Default")
      (node (ref "U1") (pin "81") (pinfunction "5V_81") (pintype "unspecified"))
    )
    (net (code "107") (name "unconnected-(U1-5V-Pad82)") (class "Default")
      (node (ref "U1") (pin "82") (pinfunction "5V_82") (pintype "unspecified"))
    )
    (net (code "108") (name "unconnected-(U1-A0-Pad1)") (class "Default")
      (node (ref "U1") (pin "1") (pinfunction "A0_1") (pintype "unspecified"))
    )
    (net (code "109") (name "unconnected-(U1-A1-Pad2)") (class "Default")
      (node (ref "U1") (pin "2") (pinfunction "A1_2") (pintype "unspecified"))
    )
    (net (code "110") (name "unconnected-(U1-A2-Pad3)") (class "Default")
      (node (ref "U1") (pin "3") (pinfunction "A2_3") (pintype "unspecified"))
    )
    (net (code "111") (name "unconnected-(U1-A3-Pad4)") (class "Default")
      (node (ref "U1") (pin "4") (pinfunction "A3_4") (pintype "unspecified"))
    )
    (net (code "112") (name "unconnected-(U1-A4-Pad5)") (class "Default")
      (node (ref "U1") (pin "5") (pinfunction "A4_5") (pintype "unspecified"))
    )
    (net (code "113") (name "unconnected-(U1-A5-Pad6)") (class "Default")
      (node (ref "U1") (pin "6") (pinfunction "A5_6") (pintype "unspecified"))
    )
    (net (code "114") (name "unconnected-(U1-A6-Pad7)") (class "Default")
      (node (ref "U1") (pin "7") (pinfunction "A6_7") (pintype "unspecified"))
    )
    (net (code "115") (name "unconnected-(U1-A7-Pad8)") (class "Default")
      (node (ref "U1") (pin "8") (pinfunction "A7_8") (pintype "unspecified"))
    )
    (net (code "116") (name "unconnected-(U1-A8-Pad9)") (class "Default")
      (node (ref "U1") (pin "9") (pinfunction "A8_9") (pintype "unspecified"))
    )
    (net (code "117") (name "unconnected-(U1-A9-Pad10)") (class "Default")
      (node (ref "U1") (pin "10") (pinfunction "A9_10") (pintype "unspecified"))
    )
    (net (code "118") (name "unconnected-(U1-A10-Pad11)") (class "Default")
      (node (ref "U1") (pin "11") (pinfunction "A10_11") (pintype "unspecified"))
    )
    (net (code "119") (name "unconnected-(U1-A11-Pad12)") (class "Default")
      (node (ref "U1") (pin "12") (pinfunction "A11_12") (pintype "unspecified"))
    )
    (net (code "120") (name "unconnected-(U1-A12-Pad13)") (class "Default")
      (node (ref "U1") (pin "13") (pinfunction "A12_13") (pintype "unspecified"))
    )
    (net (code "121") (name "unconnected-(U1-A13-Pad14)") (class "Default")
      (node (ref "U1") (pin "14") (pinfunction "A13_14") (pintype "unspecified"))
    )
    (net (code "122") (name "unconnected-(U1-A14-Pad15)") (class "Default")
      (node (ref "U1") (pin "15") (pinfunction "A14_15") (pintype "unspecified"))
    )
    (net (code "123") (name "unconnected-(U1-A15-Pad16)") (class "Default")
      (node (ref "U1") (pin "16") (pinfunction "A15_16") (pintype "unspecified"))
    )
    (net (code "124") (name "unconnected-(U1-AREF-Pad78)") (class "Default")
      (node (ref "U1") (pin "78") (pinfunction "AREF_78") (pintype "unspecified"))
    )
    (net (code "125") (name "unconnected-(U1-D32-Pad17)") (class "Default")
      (node (ref "U1") (pin "17") (pinfunction "D32_17") (pintype "unspecified"))
    )
    (net (code "126") (name "unconnected-(U1-D33-Pad18)") (class "Default")
      (node (ref "U1") (pin "18") (pinfunction "D33_18") (pintype "unspecified"))
    )
    (net (code "127") (name "unconnected-(U1-D34-Pad19)") (class "Default")
      (node (ref "U1") (pin "19") (pinfunction "D34_19") (pintype "unspecified"))
    )
    (net (code "128") (name "unconnected-(U1-D35-Pad20)") (class "Default")
      (node (ref "U1") (pin "20") (pinfunction "D35_20") (pintype "unspecified"))
    )
    (net (code "129") (name "unconnected-(U1-D36-Pad21)") (class "Default")
      (node (ref "U1") (pin "21") (pinfunction "D36_21") (pintype "unspecified"))
    )
    (net (code "130") (name "unconnected-(U1-D37-Pad22)") (class "Default")
      (node (ref "U1") (pin "22") (pinfunction "D37_22") (pintype "unspecified"))
    )
    (net (code "131") (name "unconnected-(U1-D38-Pad23)") (class "Default")
      (node (ref "U1") (pin "23") (pinfunction "D38_23") (pintype "unspecified"))
    )
    (net (code "132") (name "unconnected-(U1-D39-Pad24)") (class "Default")
      (node (ref "U1") (pin "24") (pinfunction "D39_24") (pintype "unspecified"))
    )
    (net (code "133") (name "unconnected-(U1-D40-Pad25)") (class "Default")
      (node (ref "U1") (pin "25") (pinfunction "D40_25") (pintype "unspecified"))
    )
    (net (code "134") (name "unconnected-(U1-D48-Pad33)") (class "Default")
      (node (ref "U1") (pin "33") (pinfunction "D48_33") (pintype "unspecified"))
    )
    (net (code "135") (name "unconnected-(U1-D49-Pad34)") (class "Default")
      (node (ref "U1") (pin "34") (pinfunction "D49_34") (pintype "unspecified"))
    )
    (net (code "136") (name "unconnected-(U1-D50-Pad35)") (class "Default")
      (node (ref "U1") (pin "35") (pinfunction "D50_35") (pintype "unspecified"))
    )
    (net (code "137") (name "unconnected-(U1-D51-Pad36)") (class "Default")
      (node (ref "U1") (pin "36") (pinfunction "D51_36") (pintype "unspecified"))
    )
    (net (code "138") (name "unconnected-(U1-D52-Pad37)") (class "Default")
      (node (ref "U1") (pin "37") (pinfunction "D52_37") (pintype "unspecified"))
    )
    (net (code "139") (name "unconnected-(U1-D53-Pad38)") (class "Default")
      (node (ref "U1") (pin "38") (pinfunction "D53_38") (pintype "unspecified"))
    )
    (net (code "140") (name "unconnected-(U1-MISO-Pad40)") (class "Default")
      (node (ref "U1") (pin "40") (pinfunction "MISO_40") (pintype "unspecified"))
    )
    (net (code "141") (name "unconnected-(U1-MOSI-Pad41)") (class "Default")
      (node (ref "U1") (pin "41") (pinfunction "MOSI_41") (pintype "unspecified"))
    )
    (net (code "142") (name "unconnected-(U1-RX-Pad76)") (class "Default")
      (node (ref "U1") (pin "76") (pinfunction "RX_76") (pintype "unspecified"))
    )
    (net (code "143") (name "unconnected-(U1-Reset-Pad44)") (class "Default")
      (node (ref "U1") (pin "44") (pinfunction "Reset_44") (pintype "unspecified"))
    )
    (net (code "144") (name "unconnected-(U1-Reset-Pad77)") (class "Default")
      (node (ref "U1") (pin "77") (pinfunction "Reset_77") (pintype "unspecified"))
    )
    (net (code "145") (name "unconnected-(U1-SCK-Pad42)") (class "Default")
      (node (ref "U1") (pin "42") (pinfunction "SCK_42") (pintype "unspecified"))
    )
    (net (code "146") (name "unconnected-(U1-TX-Pad75)") (class "Default")
      (node (ref "U1") (pin "75") (pinfunction "TX_75") (pintype "unspecified"))
    )
    (net (code "147") (name "unconnected-(U1-VIN-Pad85)") (class "Default")
      (node (ref "U1") (pin "85") (pinfunction "VIN_85") (pintype "unspecified"))
    )
    (net (code "148") (name "unconnected-(U1-VIN-Pad86)") (class "Default")
      (node (ref "U1") (pin "86") (pinfunction "VIN_86") (pintype "unspecified"))
    )
    (net (code "149") (name "unconnected-(U2-D2-Pad19)") (class "Default")
      (node (ref "U2") (pin "19") (pinfunction "D2_19") (pintype "bidirectional"))
    )
    (net (code "150") (name "unconnected-(U2-D4-Pad20)") (class "Default")
      (node (ref "U2") (pin "20") (pinfunction "D4_20") (pintype "bidirectional"))
    )
    (net (code "151") (name "unconnected-(U2-D5-Pad23)") (class "Default")
      (node (ref "U2") (pin "23") (pinfunction "D5_23") (pintype "bidirectional"))
    )
    (net (code "152") (name "unconnected-(U2-D12-Pad4)") (class "Default")
      (node (ref "U2") (pin "4") (pinfunction "D12_4") (pintype "bidirectional"))
    )
    (net (code "153") (name "unconnected-(U2-D13-Pad3)") (class "Default")
      (node (ref "U2") (pin "3") (pinfunction "D13_3") (pintype "bidirectional"))
    )
    (net (code "154") (name "unconnected-(U2-D14-Pad5)") (class "Default")
      (node (ref "U2") (pin "5") (pinfunction "D14_5") (pintype "bidirectional"))
    )
    (net (code "155") (name "unconnected-(U2-D15-Pad18)") (class "Default")
      (node (ref "U2") (pin "18") (pinfunction "D15_18") (pintype "bidirectional"))
    )
    (net (code "156") (name "unconnected-(U2-D18-Pad24)") (class "Default")
      (node (ref "U2") (pin "24") (pinfunction "D18_24") (pintype "bidirectional"))
    )
    (net (code "157") (name "unconnected-(U2-D19-Pad25)") (class "Default")
      (node (ref "U2") (pin "25") (pinfunction "D19_25") (pintype "bidirectional"))
    )
    (net (code "158") (name "unconnected-(U2-D23-Pad30)") (class "Default")
      (node (ref "U2") (pin "30") (pinfunction "D23_30") (pintype "bidirectional"))
    )
    (net (code "159") (name "unconnected-(U2-D25-Pad8)") (class "Default")
      (node (ref "U2") (pin "8") (pinfunction "D25_8") (pintype "bidirectional"))
    )
    (net (code "160") (name "unconnected-(U2-D26-Pad7)") (class "Default")
      (node (ref "U2") (pin "7") (pinfunction "D26_7") (pintype "bidirectional"))
    )
    (net (code "161") (name "unconnected-(U2-D27-Pad6)") (class "Default")
      (node (ref "U2") (pin "6") (pinfunction "D27_6") (pintype "bidirectional"))
    )
    (net (code "162") (name "unconnected-(U2-D32-Pad10)") (class "Default")
      (node (ref "U2") (pin "10") (pinfunction "D32_10") (pintype "bidirectional"))
    )
    (net (code "163") (name "unconnected-(U2-D33-Pad9)") (class "Default")
      (node (ref "U2") (pin "9") (pinfunction "D33_9") (pintype "bidirectional"))
    )
    (net (code "164") (name "unconnected-(U2-D34-Pad12)") (class "Default")
      (node (ref "U2") (pin "12") (pinfunction "D34_12") (pintype "bidirectional"))
    )
    (net (code "165") (name "unconnected-(U2-D35-Pad11)") (class "Default")
      (node (ref "U2") (pin "11") (pinfunction "D35_11") (pintype "bidirectional"))
    )
    (net (code "166") (name "unconnected-(U2-EN-Pad15)") (class "Default")
      (node (ref "U2") (pin "15") (pinfunction "EN_15") (pintype "input"))
    )
    (net (code "167") (name "unconnected-(U2-GND-Pad2)") (class "Default")
      (node (ref "U2") (pin "2") (pinfunction "GND_2") (pintype "passive"))
    )
    (net (code "168") (name "unconnected-(U2-RX0-Pad27)") (class "Default")
      (node (ref "U2") (pin "27") (pinfunction "RX0_27") (pintype "bidirectional"))
    )
    (net (code "169") (name "unconnected-(U2-RX2-Pad21)") (class "Default")
      (node (ref "U2") (pin "21") (pinfunction "RX2_21") (pintype "bidirectional"))
    )
    (net (code "170") (name "unconnected-(U2-TX0-Pad28)") (class "Default")
      (node (ref "U2") (pin "28") (pinfunction "TX0_28") (pintype "bidirectional"))
    )
    (net (code "171") (name "unconnected-(U2-TX2-Pad22)") (class "Default")
      (node (ref "U2") (pin "22") (pinfunction "TX2_22") (pintype "bidirectional"))
    )
    (net (code "172") (name "unconnected-(U2-VIN-Pad1)") (class "Default")
      (node (ref "U2") (pin "1") (pinfunction "VIN_1") (pintype "passive"))
    )
    (net (code "173") (name "unconnected-(U2-VN-Pad13)") (class "Default")
      (node (ref "U2") (pin "13") (pinfunction "VN_13") (pintype "unspecified"))
    )
    (net (code "174") (name "unconnected-(U2-VP-Pad14)") (class "Default")
      (node (ref "U2") (pin "14") (pinfunction "VP_14") (pintype "unspecified"))
    )
  )
)
